# capteur.net
KiCad netlist of a schematic drawn in EAGLE
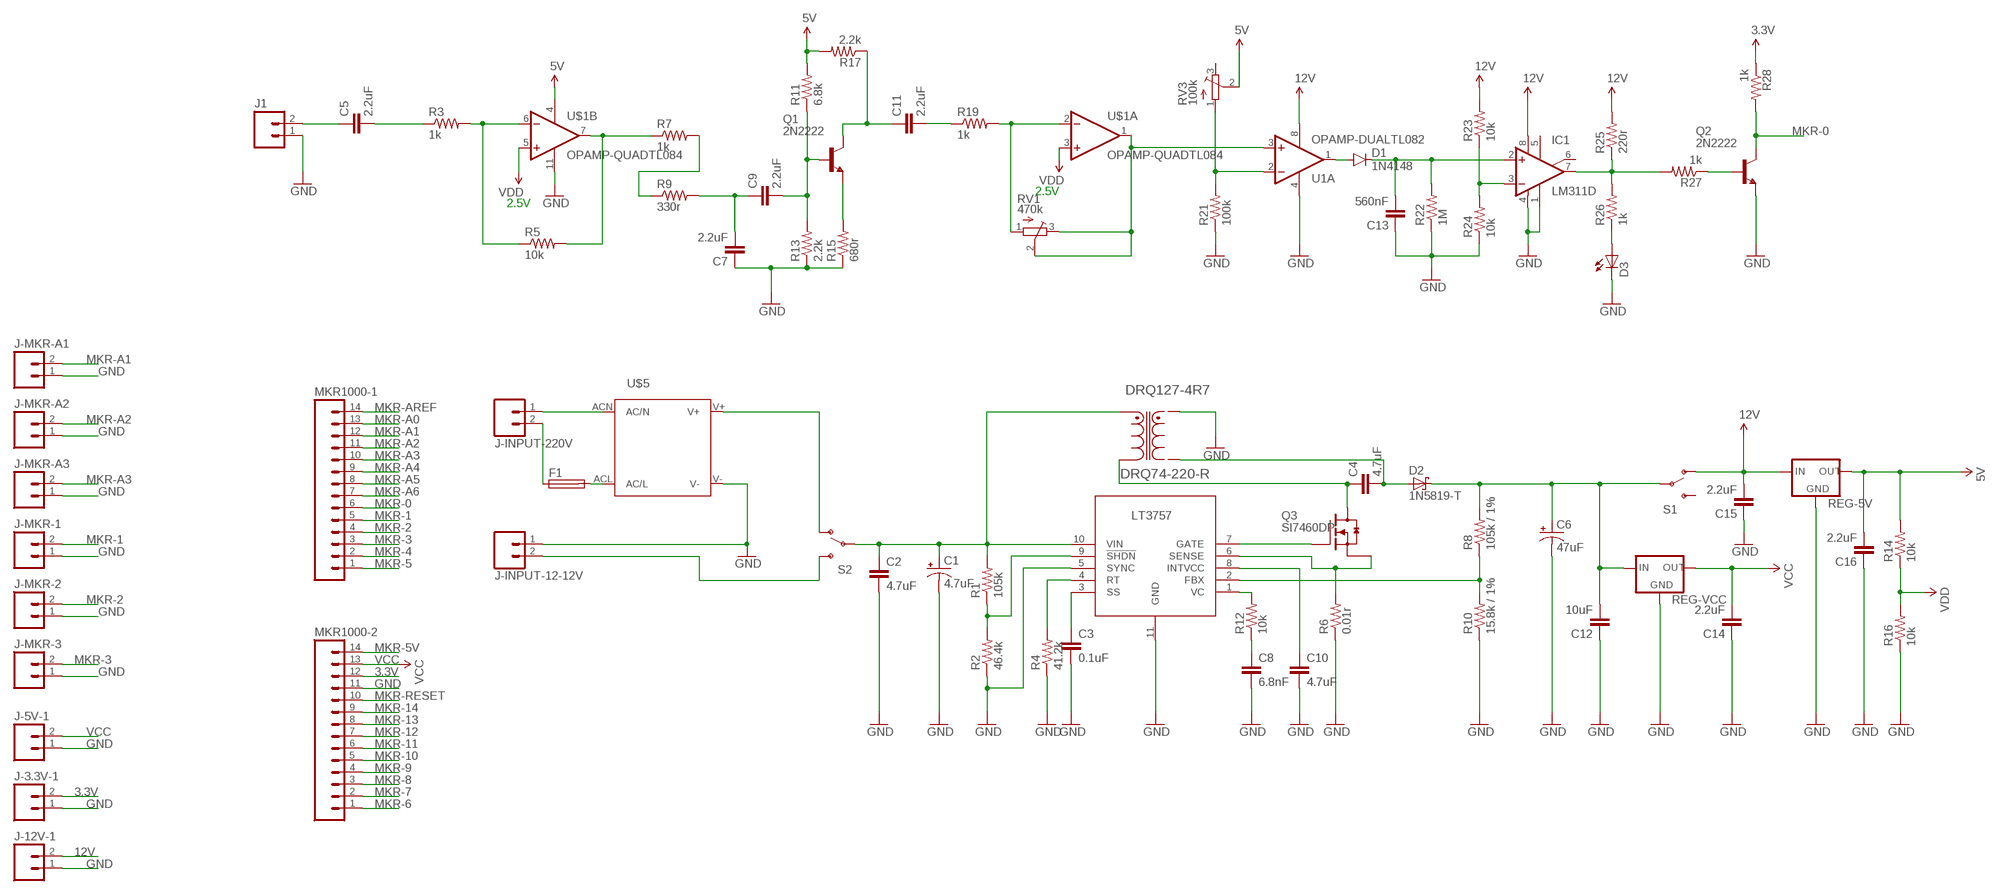
[diagram p0: schematic, sheet 1]

(export (version "E")
  (design (tool "Eeschema 10.0.6"))
  (components
    (comp (ref "C1")
      (value "4.7uF")
      (footprint "eagle-import:CPOL-RADIAL-10UF-25V")
      (libsource (lib "eagle-import") (part "SparkFun-Passives_CAP_POLPTH2"))
    )
    (comp (ref "C2")
      (value "4.7uF")
      (footprint "eagle-import:0805")
      (libsource (lib "eagle-import") (part "CAP0805"))
    )
    (comp (ref "C3")
      (value "0.1uF")
      (footprint "eagle-import:0805")
      (libsource (lib "eagle-import") (part "CAP0805"))
    )
    (comp (ref "C4")
      (value "4.7uF")
      (footprint "eagle-import:0805")
      (libsource (lib "eagle-import") (part "CAP0805"))
    )
    (comp (ref "C5")
      (value "2.2uF")
      (footprint "eagle-import:0805-CAP")
      (libsource (lib "eagle-import") (part "2.2UF-25V-+80/-20(0805)"))
    )
    (comp (ref "C6")
      (value "47uF")
      (footprint "eagle-import:EIA3216")
      (libsource (lib "eagle-import") (part "CAP_POL1206"))
    )
    (comp (ref "C7")
      (value "2.2uF")
      (footprint "eagle-import:0805-CAP")
      (libsource (lib "eagle-import") (part "2.2UF-25V-+80/-20(0805)"))
    )
    (comp (ref "C8")
      (value "6.8nF")
      (footprint "eagle-import:0805")
      (libsource (lib "eagle-import") (part "CAP0805"))
    )
    (comp (ref "C9")
      (value "2.2uF")
      (footprint "eagle-import:0805-CAP")
      (libsource (lib "eagle-import") (part "2.2UF-25V-+80/-20(0805)"))
    )
    (comp (ref "C10")
      (value "4.7uF")
      (footprint "eagle-import:0805")
      (libsource (lib "eagle-import") (part "CAP0805"))
    )
    (comp (ref "C11")
      (value "2.2uF")
      (footprint "eagle-import:0805-CAP")
      (libsource (lib "eagle-import") (part "2.2UF-25V-+80/-20(0805)"))
    )
    (comp (ref "C12")
      (value "10uF")
      (footprint "eagle-import:0805-CAP")
      (libsource (lib "eagle-import") (part "2.2UF-25V-+80/-20(0805)"))
    )
    (comp (ref "C13")
      (value "560nF")
      (footprint "eagle-import:0805-CAP")
      (libsource (lib "eagle-import") (part "2.2UF-25V-+80/-20(0805)"))
    )
    (comp (ref "C14")
      (value "2.2uF")
      (footprint "eagle-import:0805-CAP")
      (libsource (lib "eagle-import") (part "2.2UF-25V-+80/-20(0805)"))
    )
    (comp (ref "C15")
      (value "2.2uF")
      (footprint "eagle-import:0805-CAP")
      (libsource (lib "eagle-import") (part "2.2UF-25V-+80/-20(0805)"))
    )
    (comp (ref "C16")
      (value "2.2uF")
      (footprint "eagle-import:0805-CAP")
      (libsource (lib "eagle-import") (part "2.2UF-25V-+80/-20(0805)"))
    )
    (comp (ref "D1")
      (value "1N4148")
      (footprint "eagle-import:SOD-123")
      (libsource (lib "eagle-import") (part "DIODESOD123"))
    )
    (comp (ref "D2")
      (value "1N5819-T")
      (footprint "eagle-import:DO41-7.6")
      (libsource (lib "eagle-import") (part "1N5819-T"))
    )
    (comp (ref "D3")
      (value "LEDCHIPLED_0805")
      (footprint "eagle-import:CHIPLED_0805")
      (libsource (lib "eagle-import") (part "LEDCHIPLED_0805"))
    )
    (comp (ref "DRQ127-4R7")
      (value "DRQ74-220-R")
      (footprint "eagle-import:IND_DRQ74-220-R")
      (fields (field (name "TOLERANCE") "±20%"))
      (libsource (lib "eagle-import") (part "DRQ74-220-R"))
    )
    (comp (ref "F1")
      (value "SH22,5A")
      (footprint "eagle-import:SH22,5A")
      (fields (field (name "MPN") "0031.7701.11"))
      (libsource (lib "eagle-import") (part "SH22,5A"))
    )
    (comp (ref "IC1")
      (value "LM311D")
      (footprint "eagle-import:SO08")
      (libsource (lib "eagle-import") (part "LM311D"))
    )
    (comp (ref "J-3.3V-1")
      (value "M025MM")
      (footprint "eagle-import:SCREWTERMINAL-5MM-2")
      (libsource (lib "eagle-import") (part "M025MM"))
    )
    (comp (ref "J-5V-1")
      (value "M025MM")
      (footprint "eagle-import:SCREWTERMINAL-5MM-2")
      (libsource (lib "eagle-import") (part "M025MM"))
    )
    (comp (ref "J-12V-1")
      (value "M025MM")
      (footprint "eagle-import:SCREWTERMINAL-5MM-2")
      (libsource (lib "eagle-import") (part "M025MM"))
    )
    (comp (ref "J-INPUT-12-12V")
      (value "M025MM")
      (footprint "eagle-import:SCREWTERMINAL-5MM-2")
      (libsource (lib "eagle-import") (part "M025MM"))
    )
    (comp (ref "J-INPUT-220V")
      (value "M025MM")
      (footprint "eagle-import:SCREWTERMINAL-5MM-2")
      (libsource (lib "eagle-import") (part "M025MM"))
    )
    (comp (ref "J-MKR-1")
      (value "M025MM")
      (footprint "eagle-import:SCREWTERMINAL-5MM-2")
      (libsource (lib "eagle-import") (part "M025MM"))
    )
    (comp (ref "J-MKR-2")
      (value "M025MM")
      (footprint "eagle-import:SCREWTERMINAL-5MM-2")
      (libsource (lib "eagle-import") (part "M025MM"))
    )
    (comp (ref "J-MKR-3")
      (value "M025MM")
      (footprint "eagle-import:SCREWTERMINAL-5MM-2")
      (libsource (lib "eagle-import") (part "M025MM"))
    )
    (comp (ref "J-MKR-A1")
      (value "M025MM")
      (footprint "eagle-import:SCREWTERMINAL-5MM-2")
      (libsource (lib "eagle-import") (part "M025MM"))
    )
    (comp (ref "J-MKR-A2")
      (value "M025MM")
      (footprint "eagle-import:SCREWTERMINAL-5MM-2")
      (libsource (lib "eagle-import") (part "M025MM"))
    )
    (comp (ref "J-MKR-A3")
      (value "M025MM")
      (footprint "eagle-import:SCREWTERMINAL-5MM-2")
      (libsource (lib "eagle-import") (part "M025MM"))
    )
    (comp (ref "J1")
      (value "M025MM")
      (footprint "eagle-import:SCREWTERMINAL-5MM-2")
      (libsource (lib "eagle-import") (part "M025MM"))
    )
    (comp (ref "MKR1000-1")
      (value "M14")
      (footprint "eagle-import:1X14")
      (libsource (lib "eagle-import") (part "M14"))
    )
    (comp (ref "MKR1000-2")
      (value "M14")
      (footprint "eagle-import:1X14")
      (libsource (lib "eagle-import") (part "M14"))
    )
    (comp (ref "Q1")
      (value "2N2222")
      (footprint "eagle-import:TO18")
      (libsource (lib "eagle-import") (part "2N2222"))
    )
    (comp (ref "Q2")
      (value "2N2222")
      (footprint "eagle-import:TO18")
      (libsource (lib "eagle-import") (part "2N2222"))
    )
    (comp (ref "Q3")
      (value "SI7460DP")
      (footprint "eagle-import:POWERPAK-SO-08")
      (libsource (lib "eagle-import") (part "SI7370"))
    )
    (comp (ref "R1")
      (value "105k")
      (footprint "eagle-import:0805")
      (libsource (lib "eagle-import") (part "RESISTOR0805-RES"))
    )
    (comp (ref "R2")
      (value "46.4k")
      (footprint "eagle-import:0805")
      (libsource (lib "eagle-import") (part "RESISTOR0805-RES"))
    )
    (comp (ref "R3")
      (value "1k")
      (footprint "eagle-import:0805")
      (libsource (lib "eagle-import") (part "RESISTOR0805-RES"))
    )
    (comp (ref "R4")
      (value "41.2k")
      (footprint "eagle-import:0805")
      (libsource (lib "eagle-import") (part "RESISTOR0805-RES"))
    )
    (comp (ref "R5")
      (value "10k")
      (footprint "eagle-import:0805")
      (libsource (lib "eagle-import") (part "RESISTOR0805-RES"))
    )
    (comp (ref "R6")
      (value "0.01r")
      (footprint "eagle-import:2512")
      (libsource (lib "eagle-import") (part "0.001OHM-3W-1%(2512)3W/1%"))
    )
    (comp (ref "R7")
      (value "1k")
      (footprint "eagle-import:0805")
      (libsource (lib "eagle-import") (part "RESISTOR0805-RES"))
    )
    (comp (ref "R8")
      (value "105k / 1%")
      (footprint "eagle-import:0805")
      (libsource (lib "eagle-import") (part "RESISTOR0805-RES"))
    )
    (comp (ref "R9")
      (value "330r")
      (footprint "eagle-import:0805")
      (libsource (lib "eagle-import") (part "RESISTOR0805-RES"))
    )
    (comp (ref "R10")
      (value "15.8k / 1%")
      (footprint "eagle-import:0805")
      (libsource (lib "eagle-import") (part "RESISTOR0805-RES"))
    )
    (comp (ref "R11")
      (value "6.8k")
      (footprint "eagle-import:0805")
      (libsource (lib "eagle-import") (part "RESISTOR0805-RES"))
    )
    (comp (ref "R12")
      (value "10k")
      (footprint "eagle-import:0805")
      (libsource (lib "eagle-import") (part "RESISTOR0805-RES"))
    )
    (comp (ref "R13")
      (value "2.2k")
      (footprint "eagle-import:0805")
      (libsource (lib "eagle-import") (part "RESISTOR0805-RES"))
    )
    (comp (ref "R14")
      (value "10k")
      (footprint "eagle-import:0805")
      (libsource (lib "eagle-import") (part "RESISTOR0805-RES"))
    )
    (comp (ref "R15")
      (value "680r")
      (footprint "eagle-import:0805")
      (libsource (lib "eagle-import") (part "RESISTOR0805-RES"))
    )
    (comp (ref "R16")
      (value "10k")
      (footprint "eagle-import:0805")
      (libsource (lib "eagle-import") (part "RESISTOR0805-RES"))
    )
    (comp (ref "R17")
      (value "2.2k")
      (footprint "eagle-import:0805")
      (libsource (lib "eagle-import") (part "RESISTOR0805-RES"))
    )
    (comp (ref "R19")
      (value "1k")
      (footprint "eagle-import:0805")
      (libsource (lib "eagle-import") (part "RESISTOR0805-RES"))
    )
    (comp (ref "R21")
      (value "100k")
      (footprint "eagle-import:0805")
      (libsource (lib "eagle-import") (part "RESISTOR0805-RES"))
    )
    (comp (ref "R22")
      (value "1M")
      (footprint "eagle-import:0805")
      (libsource (lib "eagle-import") (part "RESISTOR0805-RES"))
    )
    (comp (ref "R23")
      (value "10k")
      (footprint "eagle-import:0805")
      (libsource (lib "eagle-import") (part "RESISTOR0805-RES"))
    )
    (comp (ref "R24")
      (value "10k")
      (footprint "eagle-import:0805")
      (libsource (lib "eagle-import") (part "RESISTOR0805-RES"))
    )
    (comp (ref "R25")
      (value "220r")
      (footprint "eagle-import:0805")
      (libsource (lib "eagle-import") (part "RESISTOR0805-RES"))
    )
    (comp (ref "R26")
      (value "1k")
      (footprint "eagle-import:0805")
      (libsource (lib "eagle-import") (part "RESISTOR0805-RES"))
    )
    (comp (ref "R27")
      (value "1k")
      (footprint "eagle-import:0805")
      (libsource (lib "eagle-import") (part "RESISTOR0805-RES"))
    )
    (comp (ref "R28")
      (value "1k")
      (footprint "eagle-import:0805")
      (libsource (lib "eagle-import") (part "RESISTOR0805-RES"))
    )
    (comp (ref "REG-5V")
      (value "V_REG_78XXTO-92_UNTESTED")
      (footprint "eagle-import:TO-92")
      (libsource (lib "eagle-import") (part "V_REG_78XXTO-92_UNTESTED"))
    )
    (comp (ref "REG-VCC")
      (value "V_REG_78XXTO-92_UNTESTED")
      (footprint "eagle-import:TO-92")
      (libsource (lib "eagle-import") (part "V_REG_78XXTO-92_UNTESTED"))
    )
    (comp (ref "RV1")
      (value "470k")
      (footprint "eagle-import:SM-42_43W")
      (libsource (lib "eagle-import") (part "TRIM_EU-SM-42/43W"))
    )
    (comp (ref "RV3")
      (value "100k")
      (footprint "eagle-import:SM-42_43W")
      (libsource (lib "eagle-import") (part "TRIM_EU-SM-42/43W"))
    )
    (comp (ref "S1")
      (value "SWITCH-SPDT-1")
      (footprint "eagle-import:MHS122-1")
      (libsource (lib "eagle-import") (part "SWITCH-SPDT-1"))
    )
    (comp (ref "S2")
      (value "SWITCH-SPDT-1")
      (footprint "eagle-import:MHS122-1")
      (libsource (lib "eagle-import") (part "SWITCH-SPDT-1"))
    )
    (comp (ref "U$1")
      (value "OPAMP-QUADTL084")
      (footprint "eagle-import:DIP14")
      (libsource (lib "eagle-import") (part "OPAMP-QUADTL084"))
    )
    (comp (ref "U$3")
      (value "LT3757")
      (footprint "eagle-import:10-MSOP-EP")
      (libsource (lib "eagle-import") (part "LT3757"))
    )
    (comp (ref "U$5")
      (value "IRM_45/60IRM_45/60")
      (footprint "eagle-import:IRM_45_60")
      (libsource (lib "eagle-import") (part "IRM_45/60IRM_45/60"))
    )
    (comp (ref "U1")
      (value "OPAMP-DUALTL082")
      (footprint "eagle-import:DIP8")
      (libsource (lib "eagle-import") (part "OPAMP-DUALTL082"))
    )
  )
  (nets
    (net (code "1") (name "/MKR-0") (class "Default")
      (node (ref "MKR1000-1") (pin "6") (pinfunction "6_6") (pintype "passive"))
      (node (ref "Q2") (pin "3") (pinfunction "C_3") (pintype "passive"))
      (node (ref "R28") (pin "2") (pinfunction "2_2") (pintype "passive"))
    )
    (net (code "2") (name "/MKR-1") (class "Default")
      (node (ref "J-MKR-1") (pin "2") (pinfunction "2_2") (pintype "passive"))
      (node (ref "MKR1000-1") (pin "5") (pinfunction "5_5") (pintype "passive"))
    )
    (net (code "3") (name "/MKR-2") (class "Default")
      (node (ref "J-MKR-2") (pin "2") (pinfunction "2_2") (pintype "passive"))
      (node (ref "MKR1000-1") (pin "4") (pinfunction "4_4") (pintype "passive"))
    )
    (net (code "4") (name "/MKR-3") (class "Default")
      (node (ref "J-MKR-3") (pin "2") (pinfunction "2_2") (pintype "passive"))
      (node (ref "MKR1000-1") (pin "3") (pinfunction "3_3") (pintype "passive"))
    )
    (net (code "5") (name "/MKR-4") (class "Default")
      (node (ref "MKR1000-1") (pin "2") (pinfunction "2_2") (pintype "passive"))
    )
    (net (code "6") (name "/MKR-5") (class "Default")
      (node (ref "MKR1000-1") (pin "1") (pinfunction "1_1") (pintype "passive"))
    )
    (net (code "7") (name "/MKR-5V") (class "Default")
      (node (ref "MKR1000-2") (pin "14") (pinfunction "14_14") (pintype "passive"))
    )
    (net (code "8") (name "/MKR-6") (class "Default")
      (node (ref "MKR1000-2") (pin "1") (pinfunction "1_1") (pintype "passive"))
    )
    (net (code "9") (name "/MKR-7") (class "Default")
      (node (ref "MKR1000-2") (pin "2") (pinfunction "2_2") (pintype "passive"))
    )
    (net (code "10") (name "/MKR-8") (class "Default")
      (node (ref "MKR1000-2") (pin "3") (pinfunction "3_3") (pintype "passive"))
    )
    (net (code "11") (name "/MKR-9") (class "Default")
      (node (ref "MKR1000-2") (pin "4") (pinfunction "4_4") (pintype "passive"))
    )
    (net (code "12") (name "/MKR-10") (class "Default")
      (node (ref "MKR1000-2") (pin "5") (pinfunction "5_5") (pintype "passive"))
    )
    (net (code "13") (name "/MKR-11") (class "Default")
      (node (ref "MKR1000-2") (pin "6") (pinfunction "6_6") (pintype "passive"))
    )
    (net (code "14") (name "/MKR-12") (class "Default")
      (node (ref "MKR1000-2") (pin "7") (pinfunction "7_7") (pintype "passive"))
    )
    (net (code "15") (name "/MKR-13") (class "Default")
      (node (ref "MKR1000-2") (pin "8") (pinfunction "8_8") (pintype "passive"))
    )
    (net (code "16") (name "/MKR-14") (class "Default")
      (node (ref "MKR1000-2") (pin "9") (pinfunction "9_9") (pintype "passive"))
    )
    (net (code "17") (name "/MKR-A0") (class "Default")
      (node (ref "MKR1000-1") (pin "13") (pinfunction "13_13") (pintype "passive"))
    )
    (net (code "18") (name "/MKR-A1") (class "Default")
      (node (ref "J-MKR-A1") (pin "2") (pinfunction "2_2") (pintype "passive"))
      (node (ref "MKR1000-1") (pin "12") (pinfunction "12_12") (pintype "passive"))
    )
    (net (code "19") (name "/MKR-A2") (class "Default")
      (node (ref "J-MKR-A2") (pin "2") (pinfunction "2_2") (pintype "passive"))
      (node (ref "MKR1000-1") (pin "11") (pinfunction "11_11") (pintype "passive"))
    )
    (net (code "20") (name "/MKR-A3") (class "Default")
      (node (ref "J-MKR-A3") (pin "2") (pinfunction "2_2") (pintype "passive"))
      (node (ref "MKR1000-1") (pin "10") (pinfunction "10_10") (pintype "passive"))
    )
    (net (code "21") (name "/MKR-A4") (class "Default")
      (node (ref "MKR1000-1") (pin "9") (pinfunction "9_9") (pintype "passive"))
    )
    (net (code "22") (name "/MKR-A5") (class "Default")
      (node (ref "MKR1000-1") (pin "8") (pinfunction "8_8") (pintype "passive"))
    )
    (net (code "23") (name "/MKR-A6") (class "Default")
      (node (ref "MKR1000-1") (pin "7") (pinfunction "7_7") (pintype "passive"))
    )
    (net (code "24") (name "/MKR-AREF") (class "Default")
      (node (ref "MKR1000-1") (pin "14") (pinfunction "14_14") (pintype "passive"))
    )
    (net (code "25") (name "/MKR-RESET") (class "Default")
      (node (ref "MKR1000-2") (pin "10") (pinfunction "10_10") (pintype "passive"))
    )
    (net (code "26") (name "3.3V") (class "Default")
      (node (ref "J-3.3V-1") (pin "2") (pinfunction "2_2") (pintype "passive"))
      (node (ref "MKR1000-2") (pin "12") (pinfunction "12_12") (pintype "passive"))
      (node (ref "R28") (pin "1") (pinfunction "1_1") (pintype "passive"))
    )
    (net (code "27") (name "5V") (class "Default")
      (node (ref "C16") (pin "2") (pinfunction "2_2") (pintype "passive"))
      (node (ref "R11") (pin "2") (pinfunction "2_2") (pintype "passive"))
      (node (ref "R14") (pin "2") (pinfunction "2_2") (pintype "passive"))
      (node (ref "R17") (pin "2") (pinfunction "2_2") (pintype "passive"))
      (node (ref "REG-5V") (pin "1") (pinfunction "OUT_1") (pintype "passive"))
      (node (ref "RV3") (pin "2") (pinfunction "S_2") (pintype "passive"))
      (node (ref "U$1") (pin "4") (pinfunction "VCC_4") (pintype "power_in"))
    )
    (net (code "28") (name "12V") (class "Default")
      (node (ref "C15") (pin "2") (pinfunction "2_2") (pintype "passive"))
      (node (ref "IC1") (pin "8") (pinfunction "V+_8") (pintype "power_in"))
      (node (ref "J-12V-1") (pin "2") (pinfunction "2_2") (pintype "passive"))
      (node (ref "R23") (pin "2") (pinfunction "2_2") (pintype "passive"))
      (node (ref "R25") (pin "2") (pinfunction "2_2") (pintype "passive"))
      (node (ref "REG-5V") (pin "3") (pinfunction "IN_3") (pintype "input"))
      (node (ref "S1") (pin "1") (pinfunction "O_1") (pintype "passive"))
      (node (ref "U1") (pin "8") (pinfunction "VCC_8") (pintype "power_in"))
    )
    (net (code "29") (name "GND") (class "Default")
      (node (ref "C1") (pin "2") (pinfunction "-_2") (pintype "passive"))
      (node (ref "C10") (pin "2") (pinfunction "2_2") (pintype "passive"))
      (node (ref "C12") (pin "1") (pinfunction "1_1") (pintype "passive"))
      (node (ref "C13") (pin "1") (pinfunction "1_1") (pintype "passive"))
      (node (ref "C14") (pin "1") (pinfunction "1_1") (pintype "passive"))
      (node (ref "C15") (pin "1") (pinfunction "1_1") (pintype "passive"))
      (node (ref "C16") (pin "1") (pinfunction "1_1") (pintype "passive"))
      (node (ref "C2") (pin "2") (pinfunction "2_2") (pintype "passive"))
      (node (ref "C3") (pin "2") (pinfunction "2_2") (pintype "passive"))
      (node (ref "C6") (pin "C") (pinfunction "-_C") (pintype "passive"))
      (node (ref "C7") (pin "1") (pinfunction "1_1") (pintype "passive"))
      (node (ref "C8") (pin "2") (pinfunction "2_2") (pintype "passive"))
      (node (ref "D3") (pin "C") (pinfunction "C_C") (pintype "passive"))
      (node (ref "DRQ127-4R7") (pin "2") (pinfunction "2_2") (pintype "passive"))
      (node (ref "IC1") (pin "1") (pinfunction "GND_1") (pintype "passive"))
      (node (ref "IC1") (pin "4") (pinfunction "V-_4") (pintype "power_in"))
      (node (ref "J-12V-1") (pin "1") (pinfunction "1_1") (pintype "passive"))
      (node (ref "J-3.3V-1") (pin "1") (pinfunction "1_1") (pintype "passive"))
      (node (ref "J-5V-1") (pin "1") (pinfunction "1_1") (pintype "passive"))
      (node (ref "J-INPUT-12-12V") (pin "1") (pinfunction "1_1") (pintype "passive"))
      (node (ref "J-MKR-1") (pin "1") (pinfunction "1_1") (pintype "passive"))
      (node (ref "J-MKR-2") (pin "1") (pinfunction "1_1") (pintype "passive"))
      (node (ref "J-MKR-3") (pin "1") (pinfunction "1_1") (pintype "passive"))
      (node (ref "J-MKR-A1") (pin "1") (pinfunction "1_1") (pintype "passive"))
      (node (ref "J-MKR-A2") (pin "1") (pinfunction "1_1") (pintype "passive"))
      (node (ref "J-MKR-A3") (pin "1") (pinfunction "1_1") (pintype "passive"))
      (node (ref "J1") (pin "1") (pinfunction "1_1") (pintype "passive"))
      (node (ref "MKR1000-2") (pin "11") (pinfunction "11_11") (pintype "passive"))
      (node (ref "Q2") (pin "1") (pinfunction "E_1") (pintype "passive"))
      (node (ref "R10") (pin "1") (pinfunction "1_1") (pintype "passive"))
      (node (ref "R13") (pin "1") (pinfunction "1_1") (pintype "passive"))
      (node (ref "R15") (pin "1") (pinfunction "1_1") (pintype "passive"))
      (node (ref "R16") (pin "1") (pinfunction "1_1") (pintype "passive"))
      (node (ref "R2") (pin "1") (pinfunction "1_1") (pintype "passive"))
      (node (ref "R21") (pin "1") (pinfunction "1_1") (pintype "passive"))
      (node (ref "R22") (pin "1") (pinfunction "1_1") (pintype "passive"))
      (node (ref "R24") (pin "1") (pinfunction "1_1") (pintype "passive"))
      (node (ref "R4") (pin "1") (pinfunction "1_1") (pintype "passive"))
      (node (ref "R6") (pin "1") (pinfunction "1_1") (pintype "passive"))
      (node (ref "REG-5V") (pin "2") (pinfunction "GND_2") (pintype "input"))
      (node (ref "REG-VCC") (pin "2") (pinfunction "GND_2") (pintype "input"))
      (node (ref "U$1") (pin "11") (pinfunction "VEE_11") (pintype "power_in"))
      (node (ref "U$3") (pin "11") (pinfunction "GND_11") (pintype "power_in"))
      (node (ref "U$3") (pin "5") (pinfunction "SYNC_5") (pintype "input"))
      (node (ref "U$5") (pin "V-") (pinfunction "V-_V-") (pintype "output"))
      (node (ref "U1") (pin "4") (pinfunction "VEE_4") (pintype "power_in"))
    )
    (net (code "30") (name "Net-(C1-+)") (class "Default")
      (node (ref "C1") (pin "1") (pinfunction "+_1") (pintype "passive"))
      (node (ref "C2") (pin "1") (pinfunction "1_1") (pintype "passive"))
      (node (ref "DRQ127-4R7") (pin "1") (pinfunction "1_1") (pintype "passive"))
      (node (ref "R1") (pin "2") (pinfunction "2_2") (pintype "passive"))
      (node (ref "S2") (pin "2") (pinfunction "P_2") (pintype "passive"))
      (node (ref "U$3") (pin "10") (pinfunction "VIN_10") (pintype "power_in"))
    )
    (net (code "31") (name "Net-(C4-Pad2)") (class "Default")
      (node (ref "C4") (pin "2") (pinfunction "2_2") (pintype "passive"))
      (node (ref "D2") (pin "A") (pinfunction "A_A") (pintype "passive"))
      (node (ref "DRQ127-4R7") (pin "4") (pinfunction "4_4") (pintype "passive"))
    )
    (net (code "32") (name "Net-(C5-Pad1)") (class "Default")
      (node (ref "C5") (pin "1") (pinfunction "1_1") (pintype "passive"))
      (node (ref "J1") (pin "2") (pinfunction "2_2") (pintype "passive"))
    )
    (net (code "33") (name "Net-(C5-Pad2)") (class "Default")
      (node (ref "C5") (pin "2") (pinfunction "2_2") (pintype "passive"))
      (node (ref "R3") (pin "1") (pinfunction "1_1") (pintype "passive"))
    )
    (net (code "34") (name "Net-(C6-+)") (class "Default")
      (node (ref "C12") (pin "2") (pinfunction "2_2") (pintype "passive"))
      (node (ref "C6") (pin "A") (pinfunction "+_A") (pintype "passive"))
      (node (ref "D2") (pin "C") (pinfunction "C_C") (pintype "passive"))
      (node (ref "R8") (pin "2") (pinfunction "2_2") (pintype "passive"))
      (node (ref "REG-VCC") (pin "3") (pinfunction "IN_3") (pintype "input"))
      (node (ref "S1") (pin "2") (pinfunction "P_2") (pintype "passive"))
    )
    (net (code "35") (name "Net-(C7-Pad2)") (class "Default")
      (node (ref "C7") (pin "2") (pinfunction "2_2") (pintype "passive"))
      (node (ref "C9") (pin "1") (pinfunction "1_1") (pintype "passive"))
      (node (ref "R9") (pin "2") (pinfunction "2_2") (pintype "passive"))
    )
    (net (code "36") (name "Net-(C8-Pad1)") (class "Default")
      (node (ref "C8") (pin "1") (pinfunction "1_1") (pintype "passive"))
      (node (ref "R12") (pin "1") (pinfunction "1_1") (pintype "passive"))
    )
    (net (code "37") (name "Net-(C11-Pad2)") (class "Default")
      (node (ref "C11") (pin "2") (pinfunction "2_2") (pintype "passive"))
      (node (ref "R19") (pin "1") (pinfunction "1_1") (pintype "passive"))
    )
    (net (code "38") (name "Net-(D3-PadA)") (class "Default")
      (node (ref "D3") (pin "A") (pinfunction "A_A") (pintype "passive"))
      (node (ref "R26") (pin "1") (pinfunction "1_1") (pintype "passive"))
    )
    (net (code "39") (name "Net-(F1-Pad1)") (class "Default")
      (node (ref "F1") (pin "1") (pinfunction "1_1") (pintype "passive"))
      (node (ref "J-INPUT-220V") (pin "2") (pinfunction "2_2") (pintype "passive"))
    )
    (net (code "40") (name "Net-(IC1-+IN)") (class "Default")
      (node (ref "C13") (pin "2") (pinfunction "2_2") (pintype "passive"))
      (node (ref "D1") (pin "C") (pinfunction "C_C") (pintype "passive"))
      (node (ref "IC1") (pin "2") (pinfunction "+IN_2") (pintype "input"))
      (node (ref "R22") (pin "2") (pinfunction "2_2") (pintype "passive"))
    )
    (net (code "41") (name "Net-(IC1--IN)") (class "Default")
      (node (ref "IC1") (pin "3") (pinfunction "-IN_3") (pintype "input"))
      (node (ref "R23") (pin "1") (pinfunction "1_1") (pintype "passive"))
      (node (ref "R24") (pin "2") (pinfunction "2_2") (pintype "passive"))
    )
    (net (code "42") (name "Net-(IC1-OUT)") (class "Default")
      (node (ref "IC1") (pin "7") (pinfunction "OUT_7") (pintype "output"))
      (node (ref "R25") (pin "1") (pinfunction "1_1") (pintype "passive"))
      (node (ref "R26") (pin "2") (pinfunction "2_2") (pintype "passive"))
      (node (ref "R27") (pin "2") (pinfunction "2_2") (pintype "passive"))
    )
    (net (code "43") (name "Net-(Q1-B)") (class "Default")
      (node (ref "C9") (pin "2") (pinfunction "2_2") (pintype "passive"))
      (node (ref "Q1") (pin "2") (pinfunction "B_2") (pintype "passive"))
      (node (ref "R11") (pin "1") (pinfunction "1_1") (pintype "passive"))
      (node (ref "R13") (pin "2") (pinfunction "2_2") (pintype "passive"))
    )
    (net (code "44") (name "Net-(Q1-C)") (class "Default")
      (node (ref "C11") (pin "1") (pinfunction "1_1") (pintype "passive"))
      (node (ref "Q1") (pin "3") (pinfunction "C_3") (pintype "passive"))
      (node (ref "R17") (pin "1") (pinfunction "1_1") (pintype "passive"))
    )
    (net (code "45") (name "Net-(Q1-E)") (class "Default")
      (node (ref "Q1") (pin "1") (pinfunction "E_1") (pintype "passive"))
      (node (ref "R15") (pin "2") (pinfunction "2_2") (pintype "passive"))
    )
    (net (code "46") (name "Net-(Q2-B)") (class "Default")
      (node (ref "Q2") (pin "2") (pinfunction "B_2") (pintype "passive"))
      (node (ref "R27") (pin "1") (pinfunction "1_1") (pintype "passive"))
    )
    (net (code "47") (name "Net-(Q3-D)") (class "Default")
      (node (ref "C4") (pin "1") (pinfunction "1_1") (pintype "passive"))
      (node (ref "DRQ127-4R7") (pin "3") (pinfunction "3_3") (pintype "passive"))
      (node (ref "Q3") (pin "5-8") (pinfunction "D_5-8") (pintype "passive"))
    )
    (net (code "48") (name "Net-(Q3-G)") (class "Default")
      (node (ref "Q3") (pin "4") (pinfunction "G_4") (pintype "passive"))
      (node (ref "U$3") (pin "7") (pinfunction "GATE_7") (pintype "output"))
    )
    (net (code "49") (name "Net-(Q3-S3)") (class "Default")
      (node (ref "Q3") (pin "3") (pinfunction "S3_3") (pintype "passive"))
      (node (ref "R6") (pin "2") (pinfunction "2_2") (pintype "passive"))
      (node (ref "U$3") (pin "6") (pinfunction "SENSE_6") (pintype "input"))
    )
    (net (code "50") (name "Net-(R7-Pad2)") (class "Default")
      (node (ref "R7") (pin "2") (pinfunction "2_2") (pintype "passive"))
      (node (ref "R9") (pin "1") (pinfunction "1_1") (pintype "passive"))
    )
    (net (code "51") (name "Net-(RV1-A)") (class "Default")
      (node (ref "R19") (pin "2") (pinfunction "2_2") (pintype "passive"))
      (node (ref "RV1") (pin "1") (pinfunction "A_1") (pintype "passive"))
      (node (ref "U$1") (pin "2") (pinfunction "IN-_2") (pintype "input"))
    )
    (net (code "52") (name "Net-(RV1-E)") (class "Default")
      (node (ref "RV1") (pin "2") (pinfunction "S_2") (pintype "passive"))
      (node (ref "RV1") (pin "3") (pinfunction "E_3") (pintype "passive"))
      (node (ref "U$1") (pin "1") (pinfunction "OUT_1") (pintype "output"))
      (node (ref "U1") (pin "3") (pinfunction "IN+_3") (pintype "input"))
    )
    (net (code "53") (name "Net-(RV3-A)") (class "Default")
      (node (ref "R21") (pin "2") (pinfunction "2_2") (pintype "passive"))
      (node (ref "RV3") (pin "1") (pinfunction "A_1") (pintype "passive"))
      (node (ref "U1") (pin "2") (pinfunction "IN-_2") (pintype "input"))
    )
    (net (code "54") (name "Net-(S2-O)") (class "Default")
      (node (ref "S2") (pin "1") (pinfunction "O_1") (pintype "passive"))
      (node (ref "U$5") (pin "V+") (pinfunction "V+_V+") (pintype "output"))
    )
    (net (code "55") (name "Net-(S2-S)") (class "Default")
      (node (ref "J-INPUT-12-12V") (pin "2") (pinfunction "2_2") (pintype "passive"))
      (node (ref "S2") (pin "3") (pinfunction "S_3") (pintype "passive"))
    )
    (net (code "56") (name "Net-(U$1B-IN-)") (class "Default")
      (node (ref "R3") (pin "2") (pinfunction "2_2") (pintype "passive"))
      (node (ref "R5") (pin "1") (pinfunction "1_1") (pintype "passive"))
      (node (ref "U$1") (pin "6") (pinfunction "IN-_6") (pintype "input"))
    )
    (net (code "57") (name "Net-(U$1B-OUT)") (class "Default")
      (node (ref "R5") (pin "2") (pinfunction "2_2") (pintype "passive"))
      (node (ref "R7") (pin "1") (pinfunction "1_1") (pintype "passive"))
      (node (ref "U$1") (pin "7") (pinfunction "OUT_7") (pintype "output"))
    )
    (net (code "58") (name "Net-(U$3-FBX)") (class "Default")
      (node (ref "R10") (pin "2") (pinfunction "2_2") (pintype "passive"))
      (node (ref "R8") (pin "1") (pinfunction "1_1") (pintype "passive"))
      (node (ref "U$3") (pin "2") (pinfunction "FBX_2") (pintype "input"))
    )
    (net (code "59") (name "Net-(U$3-INTVCC)") (class "Default")
      (node (ref "C10") (pin "1") (pinfunction "1_1") (pintype "passive"))
      (node (ref "U$3") (pin "8") (pinfunction "INTVCC_8") (pintype "power_in"))
    )
    (net (code "60") (name "Net-(U$3-RT)") (class "Default")
      (node (ref "R4") (pin "2") (pinfunction "2_2") (pintype "passive"))
      (node (ref "U$3") (pin "4") (pinfunction "RT_4") (pintype "bidirectional"))
    )
    (net (code "61") (name "Net-(U$3-SS)") (class "Default")
      (node (ref "C3") (pin "1") (pinfunction "1_1") (pintype "passive"))
      (node (ref "U$3") (pin "3") (pinfunction "SS_3") (pintype "bidirectional"))
    )
    (net (code "62") (name "Net-(U$3-VC)") (class "Default")
      (node (ref "R12") (pin "2") (pinfunction "2_2") (pintype "passive"))
      (node (ref "U$3") (pin "1") (pinfunction "VC_1") (pintype "bidirectional"))
    )
    (net (code "63") (name "Net-(U$3-~{SHDN})") (class "Default")
      (node (ref "R1") (pin "1") (pinfunction "1_1") (pintype "passive"))
      (node (ref "R2") (pin "2") (pinfunction "2_2") (pintype "passive"))
      (node (ref "U$3") (pin "9") (pinfunction "~{SHDN}_9") (pintype "input"))
    )
    (net (code "64") (name "Net-(U$5-AC{slash}L)") (class "Default")
      (node (ref "F1") (pin "2") (pinfunction "2_2") (pintype "passive"))
      (node (ref "U$5") (pin "ACL") (pinfunction "AC/L_ACL") (pintype "input"))
    )
    (net (code "65") (name "Net-(U$5-AC{slash}N)") (class "Default")
      (node (ref "J-INPUT-220V") (pin "1") (pinfunction "1_1") (pintype "passive"))
      (node (ref "U$5") (pin "ACN") (pinfunction "AC/N_ACN") (pintype "input"))
    )
    (net (code "66") (name "Net-(U1A-OUT)") (class "Default")
      (node (ref "D1") (pin "A") (pinfunction "A_A") (pintype "passive"))
      (node (ref "U1") (pin "1") (pinfunction "OUT_1") (pintype "output"))
    )
    (net (code "67") (name "VCC") (class "Default")
      (node (ref "C14") (pin "2") (pinfunction "2_2") (pintype "passive"))
      (node (ref "J-5V-1") (pin "2") (pinfunction "2_2") (pintype "passive"))
      (node (ref "MKR1000-2") (pin "13") (pinfunction "13_13") (pintype "passive"))
      (node (ref "REG-VCC") (pin "1") (pinfunction "OUT_1") (pintype "passive"))
    )
    (net (code "68") (name "VDD") (class "Default")
      (node (ref "R14") (pin "1") (pinfunction "1_1") (pintype "passive"))
      (node (ref "R16") (pin "2") (pinfunction "2_2") (pintype "passive"))
      (node (ref "U$1") (pin "3") (pinfunction "IN+_3") (pintype "input"))
      (node (ref "U$1") (pin "5") (pinfunction "IN+_5") (pintype "input"))
    )
    (net (code "69") (name "unconnected-(IC1-ON-Pad5)") (class "Default")
      (node (ref "IC1") (pin "5") (pinfunction "ON_5") (pintype "passive"))
    )
    (net (code "70") (name "unconnected-(IC1-ON{slash}STR-Pad6)") (class "Default")
      (node (ref "IC1") (pin "6") (pinfunction "ON/STR_6") (pintype "passive"))
    )
    (net (code "71") (name "unconnected-(Q3-S1-Pad1)") (class "Default")
      (node (ref "Q3") (pin "1") (pinfunction "S1_1") (pintype "passive"))
    )
    (net (code "72") (name "unconnected-(Q3-S2-Pad2)") (class "Default")
      (node (ref "Q3") (pin "2") (pinfunction "S2_2") (pintype "passive"))
    )
    (net (code "73") (name "unconnected-(RV3-E-Pad3)") (class "Default")
      (node (ref "RV3") (pin "3") (pinfunction "E_3") (pintype "passive"))
    )
    (net (code "74") (name "unconnected-(S1-S-Pad3)") (class "Default")
      (node (ref "S1") (pin "3") (pinfunction "S_3") (pintype "passive"))
    )
  )
)
